# Analog_Mux.net
KiCad netlist of a schematic drawn in Altium Designer
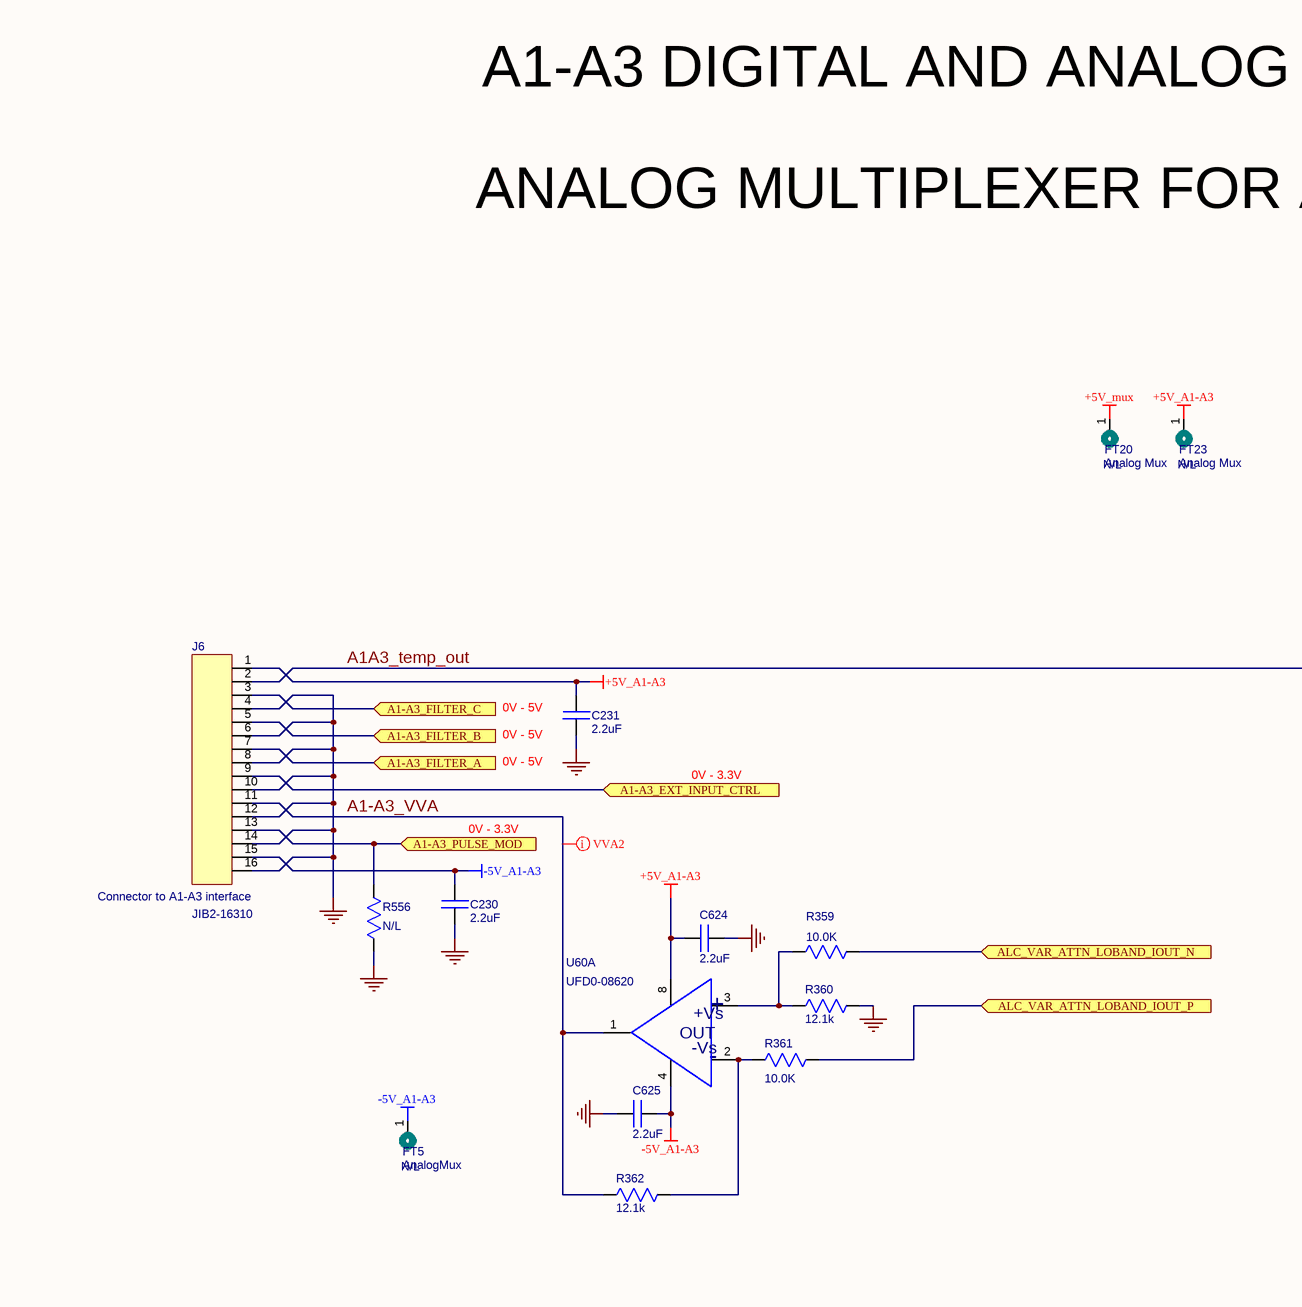
[diagram p0: Analog Mux.SchDoc, top left]
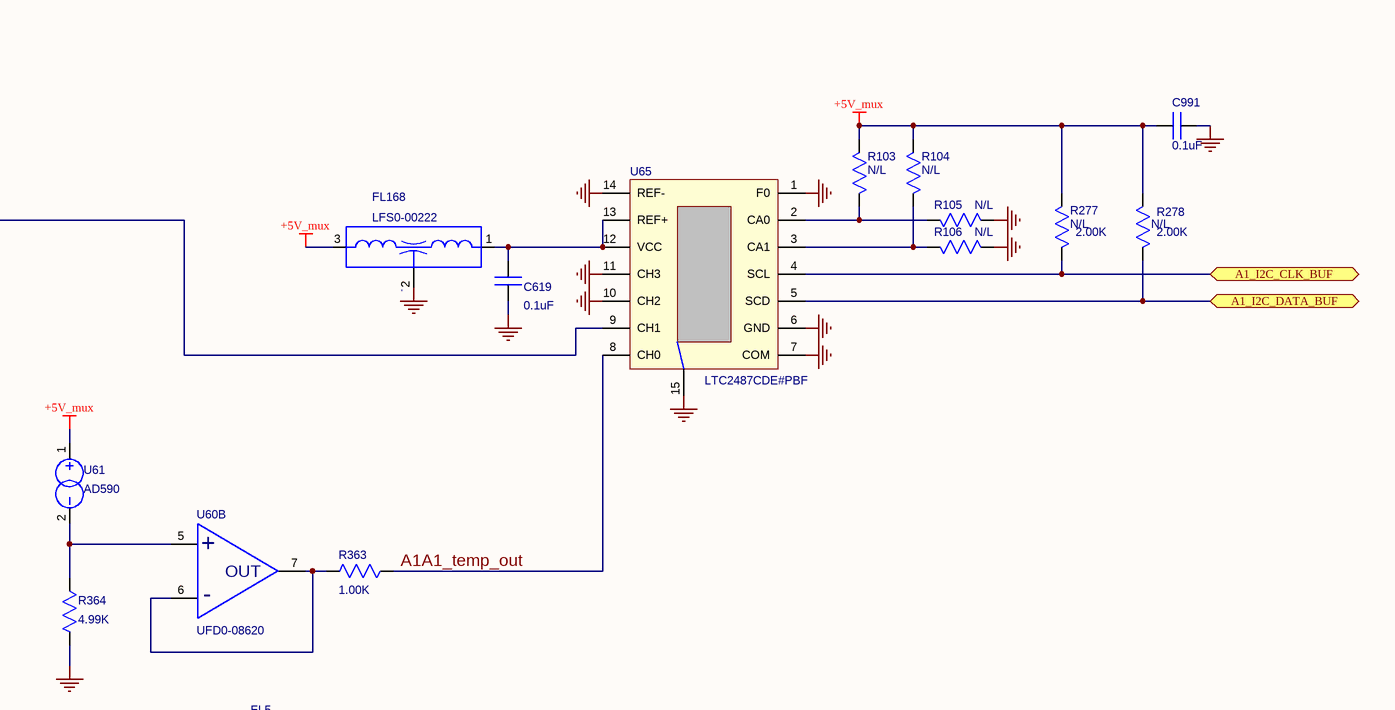
[diagram p1: Analog Mux.SchDoc, top right]
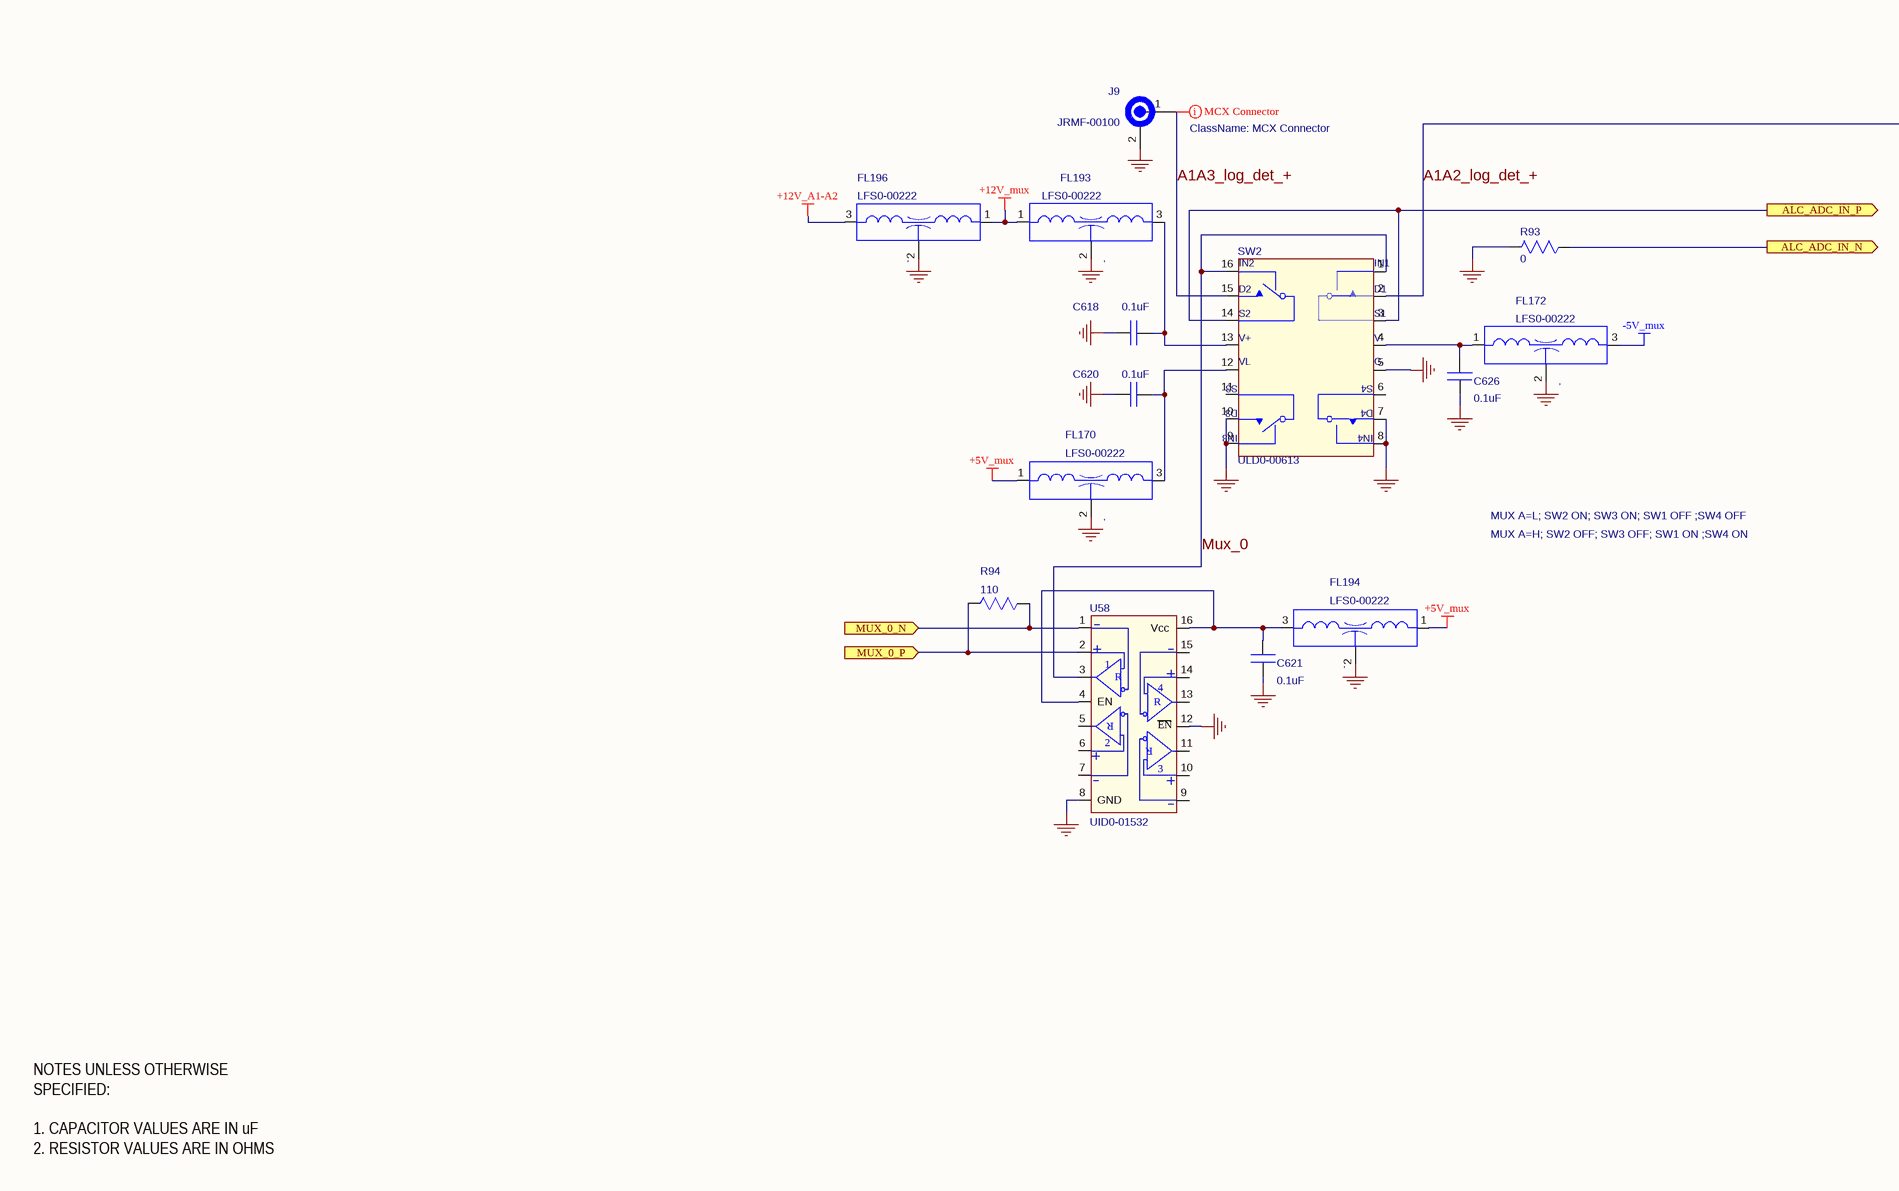
[diagram p2: Analog Mux.SchDoc, bottom left]
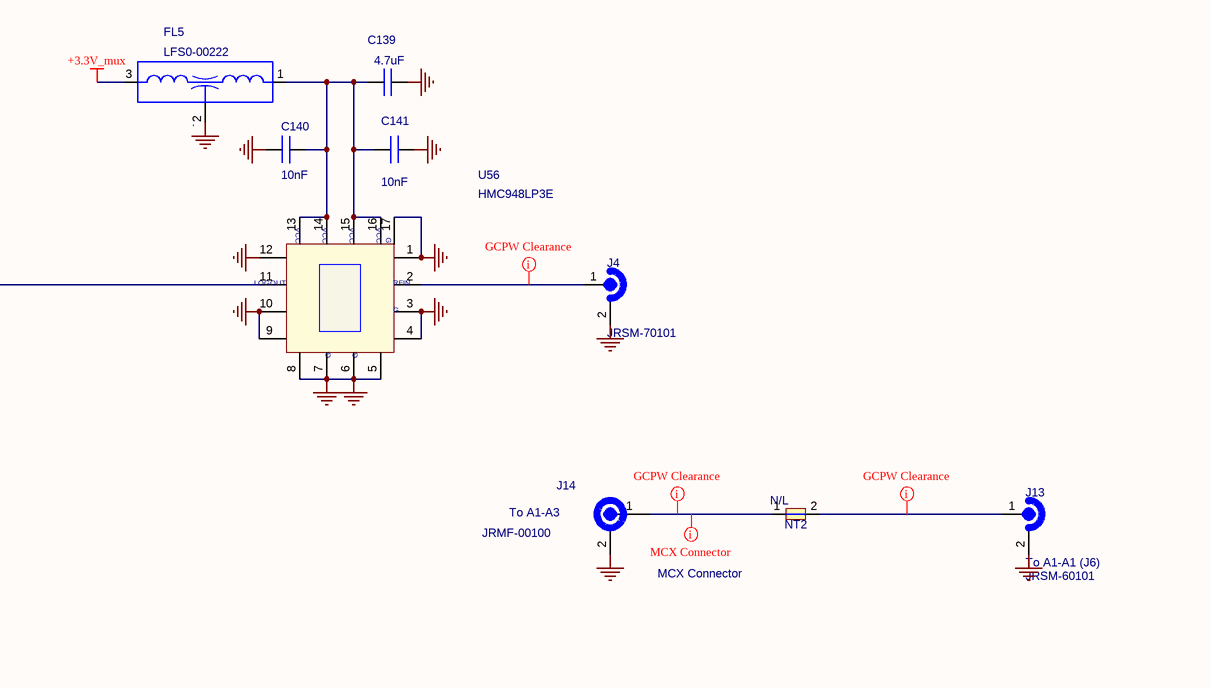
[diagram p3: Analog Mux.SchDoc, bottom right]

(export (version "E")
  (design (tool "Eeschema 10.0.6"))
  (components
    (comp (ref "C139")
      (value "4.7uF")
      (footprint "CAP-0805-N")
      (description "4.7uF 25V X5R CHIP CERAMIC")
      (fields (field (name "APPROVED") "CL"))
      (libsource (lib "Giga-tronics") (part "CK50-15470"))
    )
    (comp (ref "C140")
      (value "10nF")
      (footprint "CAP-0402-N")
      (description "10nF;10%;X7R;16 WVDC;CHIP;0402")
      (fields (field (name "APPROVED") "CL"))
      (libsource (lib "Giga-tronics") (part "TCC3-03100"))
    )
    (comp (ref "C141")
      (value "10nF")
      (footprint "CAP-0402-N")
      (description "10nF;10%;X7R;16 WVDC;CHIP;0402")
      (fields (field (name "APPROVED") "CL"))
      (libsource (lib "Giga-tronics") (part "TCC3-03100"))
    )
    (comp (ref "C230")
      (value "2.2uF")
      (footprint "CAP-0603-H035-N")
      (description "CAP,CHP,2.2UF,10%,X5R;16V")
      (fields (field (name "APPROVED") "CL"))
      (libsource (lib "Giga-tronics") (part "CK45-05220"))
    )
    (comp (ref "C231")
      (value "2.2uF")
      (footprint "CAP-0603-H035-N")
      (description "CAP,CHP,2.2UF,10%,X5R;16V")
      (fields (field (name "APPROVED") "CL"))
      (libsource (lib "Giga-tronics") (part "CK45-05220"))
    )
    (comp (ref "C618")
      (value "0.1uF")
      (footprint "CAP-0805-N")
      (description ".1UF;10%;X7R;>25V;CHIP;0805")
      (fields (field (name "APPROVED") "CL"))
      (libsource (lib "Giga-tronics") (part "CK50-04100"))
    )
    (comp (ref "C619")
      (value "0.1uF")
      (footprint "CAP-0805-N")
      (description ".1UF;10%;X7R;>25V;CHIP;0805")
      (fields (field (name "APPROVED") "CL"))
      (libsource (lib "Giga-tronics") (part "CK50-04100"))
    )
    (comp (ref "C620")
      (value "0.1uF")
      (footprint "CAP-0805-N")
      (description ".1UF;10%;X7R;>25V;CHIP;0805")
      (fields (field (name "APPROVED") "CL"))
      (libsource (lib "Giga-tronics") (part "CK50-04100"))
    )
    (comp (ref "C621")
      (value "0.1uF")
      (footprint "CAP-0603-H035-N")
      (description ".1UF;10%;X7R;16V;CHIP;0603")
      (fields (field (name "APPROVED") "CL"))
      (libsource (lib "Giga-tronics") (part "CK45-04100"))
    )
    (comp (ref "C624")
      (value "2.2uF")
      (footprint "CAP-0603-H035-N")
      (description "CAP,CHP,2.2UF,10%,X5R;16V")
      (fields (field (name "APPROVED") "CL"))
      (libsource (lib "Giga-tronics") (part "CK45-05220"))
    )
    (comp (ref "C625")
      (value "2.2uF")
      (footprint "CAP-0603-H035-N")
      (description "CAP,CHP,2.2UF,10%,X5R;16V")
      (fields (field (name "APPROVED") "CL"))
      (libsource (lib "Giga-tronics") (part "CK45-05220"))
    )
    (comp (ref "C626")
      (value "0.1uF")
      (footprint "CAP-0805-N")
      (description ".1UF;10%;X7R;>25V;CHIP;0805")
      (fields (field (name "APPROVED") "CL"))
      (libsource (lib "Giga-tronics") (part "CK50-04100"))
    )
    (comp (ref "C991")
      (value "0.1uF")
      (footprint "CAP-0402-N")
      (description ".1 UF,10%;X7R;16V,CHIP;0402")
      (fields (field (name "APPROVED") "CL"))
      (libsource (lib "Giga-tronics") (part "CK40-04100"))
    )
    (comp (ref "FL5")
      (value "Filter EMI 2200PF,1206")
      (footprint "FIL-NFE31P-1206-4P")
      (fields (field (name "G_PN") "LFS0-00222") (field (name "APPROVED") "CL"))
      (libsource (lib "Giga-tronics") (part "LFS0-00222"))
    )
    (comp (ref "FL168")
      (value "Filter EMI 2200PF,1206")
      (footprint "FIL-NFE31P-1206-4P")
      (fields (field (name "G_PN") "LFS0-00222") (field (name "APPROVED") "CL"))
      (libsource (lib "Giga-tronics") (part "LFS0-00222"))
    )
    (comp (ref "FL170")
      (value "Filter EMI 2200PF,1206")
      (footprint "FIL-NFE31P-1206-4P")
      (fields (field (name "G_PN") "LFS0-00222") (field (name "APPROVED") "CL"))
      (libsource (lib "") (part "LFS0-00222_1"))
    )
    (comp (ref "FL172")
      (value "Filter EMI 2200PF,1206")
      (footprint "FIL-NFE31P-1206-4P")
      (fields (field (name "G_PN") "LFS0-00222") (field (name "APPROVED") "CL"))
      (libsource (lib "") (part "LFS0-00222_1"))
    )
    (comp (ref "FL193")
      (value "Filter EMI 2200PF,1206")
      (footprint "FIL-NFE31P-1206-4P")
      (fields (field (name "G_PN") "LFS0-00222") (field (name "APPROVED") "CL"))
      (libsource (lib "") (part "LFS0-00222_1"))
    )
    (comp (ref "FL194")
      (value "Filter EMI 2200PF,1206")
      (footprint "FIL-NFE31P-1206-4P")
      (fields (field (name "G_PN") "LFS0-00222") (field (name "APPROVED") "CL"))
      (libsource (lib "Giga-tronics") (part "LFS0-00222"))
    )
    (comp (ref "FL196")
      (value "Filter EMI 2200PF,1206")
      (footprint "FIL-NFE31P-1206-4P")
      (fields (field (name "G_PN") "LFS0-00222") (field (name "APPROVED") "CL"))
      (libsource (lib "Giga-tronics") (part "LFS0-00222"))
    )
    (comp (ref "FT5")
      (value "AnalogMux")
      (footprint "FromToNode_ML2")
      (fields (field (name "NOLOAD") "N/L") (field (name "APPROVED") "*"))
      (libsource (lib "Giga-tronics") (part "FromToNode"))
    )
    (comp (ref "FT20")
      (value "Analog Mux")
      (footprint "FromToNode_ML2")
      (fields (field (name "NOLOAD") "N/L") (field (name "APPROVED") "*"))
      (libsource (lib "Giga-tronics") (part "FromToNode"))
    )
    (comp (ref "FT23")
      (value "Analog Mux")
      (footprint "FromToNode_ML2")
      (fields (field (name "NOLOAD") "N/L") (field (name "APPROVED") "*"))
      (libsource (lib "Giga-tronics") (part "FromToNode"))
    )
    (comp (ref "J4")
      (value ".")
      (footprint "JRSM-70101")
      (description "SMPM FD MALE,STRAIGHT SMT, R/A COPLANAR, 4 PIN THRU-HOLE")
      (fields (field (name "G_PN") "JRSM-70101") (field (name "APPROVED") "CL"))
      (libsource (lib "Giga-tronics") (part "JRSM-70101"))
    )
    (comp (ref "J6")
      (value "Connector to A1-A3 interface")
      (footprint "JIB2-16310")
      (description "STRIPLINE SOCKET;2MM CTR;2X8 PIN;.31\" HT")
      (fields (field (name "G_PN") "JIB2-16310") (field (name "APPROVED") "NM"))
      (libsource (lib "Giga-tronics") (part "JIB2-16310"))
    )
    (comp (ref "J9")
      (value "A1A3 log det +")
      (footprint "JRMF-00100")
      (description "MCX F;PC MOUNT;STRAIGHT;.1 LEADSP")
      (fields (field (name "G_PN") "JRMF-00100") (field (name "APPROVED") "NM"))
      (libsource (lib "Giga-tronics") (part "JRMF-00100"))
    )
    (comp (ref "J13")
      (value "To A1-A1 (J6)")
      (footprint "JRSM-60101")
      (description "SMPM SM MALE,STRAIGHT SMT, R/A COPLANAR, 4 PIN THRU-HOLE")
      (fields (field (name "G_PN") "JRSM-60101") (field (name "APPROVED") "CL"))
      (libsource (lib "Giga-tronics") (part "JRSM-60101"))
    )
    (comp (ref "J14")
      (value "To A1-A3")
      (footprint "JRMF-00100")
      (description "MCX F;PC MOUNT;STRAIGHT;.1 LEADSP")
      (fields (field (name "G_PN") "JRMF-00100") (field (name "APPROVED") "NM"))
      (libsource (lib "Giga-tronics") (part "JRMF-00100"))
    )
    (comp (ref "NT2")
      (value "NET TIE, 10 mil line")
      (footprint "NET_TIE_10mil")
      (fields (field (name "NOLOAD") "N/L") (field (name "APPROVED") "CL"))
      (libsource (lib "Giga-tronics") (part "NET_TIE_10mil"))
    )
    (comp (ref "R93")
      (value "0")
      (footprint "RES-0402-N")
      (description "JUMPER;0 OHMS;SMT;0402")
      (fields (field (name "APPROVED") "CL"))
      (libsource (lib "Giga-tronics") (part "RK35-00000"))
    )
    (comp (ref "R94")
      (value "110")
      (footprint "RES-0402-N")
      (description "110 OHMS; 1%; .1W; 100PPM; FILM; CHIP; 0402")
      (fields (field (name "APPROVED") "CL"))
      (libsource (lib "Giga-tronics") (part "RK35-01100"))
    )
    (comp (ref "R103")
      (value "2.00K OHMS;.06W;1%;200PPM;FILM;CHIP;0402")
      (footprint "RES-0402-N")
      (fields (field (name "NOLOAD") "N/L") (field (name "APPROVED") "CL"))
      (libsource (lib "Giga-tronics") (part "RK35-12000"))
    )
    (comp (ref "R104")
      (value "2.00K OHMS;.06W;1%;200PPM;FILM;CHIP;0402")
      (footprint "RES-0402-N")
      (fields (field (name "NOLOAD") "N/L") (field (name "APPROVED") "CL"))
      (libsource (lib "Giga-tronics") (part "RK35-12000"))
    )
    (comp (ref "R105")
      (value "JUMPER;0 OHMS;SMT;0402")
      (footprint "RES-0402-N")
      (fields (field (name "NOLOAD") "N/L") (field (name "APPROVED") "CL"))
      (libsource (lib "Giga-tronics") (part "RK35-00000"))
    )
    (comp (ref "R106")
      (value "JUMPER;0 OHMS;SMT;0402")
      (footprint "RES-0402-N")
      (fields (field (name "NOLOAD") "N/L") (field (name "APPROVED") "CL"))
      (libsource (lib "Giga-tronics") (part "RK35-00000"))
    )
    (comp (ref "R277")
      (value "2.00K")
      (footprint "RES-0402-N")
      (description "2.00K OHMS;.06W;1%;200PPM;FILM;CHIP;0402")
      (fields (field (name "NOLOAD") "N/L") (field (name "APPROVED") "CL"))
      (libsource (lib "Giga-tronics") (part "RK35-12000"))
    )
    (comp (ref "R278")
      (value "2.00K")
      (footprint "RES-0402-N")
      (description "2.00K OHMS;.06W;1%;200PPM;FILM;CHIP;0402")
      (fields (field (name "NOLOAD") "N/L") (field (name "APPROVED") "CL"))
      (libsource (lib "Giga-tronics") (part "RK35-12000"))
    )
    (comp (ref "R359")
      (value "10.0K")
      (footprint "RES-0402-N")
      (description "10.0K OHMS;.06W;1%;200PPM;FILM;CHIP;0402")
      (fields (field (name "APPROVED") "CL"))
      (libsource (lib "Giga-tronics") (part "RK35-21000"))
    )
    (comp (ref "R360")
      (value "12.1k")
      (footprint "RES-0402-N")
      (description "12.1K OHMS;.06W;1%;200PPM;FILM;CHIP;0402")
      (fields (field (name "APPROVED") "CL"))
      (libsource (lib "Giga-tronics") (part "RK35-21210"))
    )
    (comp (ref "R361")
      (value "10.0K")
      (footprint "RES-0402-N")
      (description "10.0K OHMS;.06W;1%;200PPM;FILM;CHIP;0402")
      (fields (field (name "APPROVED") "CL"))
      (libsource (lib "Giga-tronics") (part "RK35-21000"))
    )
    (comp (ref "R362")
      (value "12.1k")
      (footprint "RES-0402-N")
      (description "12.1K OHMS;.06W;1%;200PPM;FILM;CHIP;0402")
      (fields (field (name "APPROVED") "CL"))
      (libsource (lib "Giga-tronics") (part "RK35-21210"))
    )
    (comp (ref "R363")
      (value "1.00K")
      (footprint "RES-0402-N")
      (description "1.0K OHMS;.06W;1%;200PPM;FILM;CHIP;0402")
      (fields (field (name "APPROVED") "CL"))
      (libsource (lib "Giga-tronics") (part "RK35-11000"))
    )
    (comp (ref "R364")
      (value "4.99K")
      (footprint "RES-0402-N")
      (description "4.99K OHMS;.06W;1%;200PPM;FILM;CHIP;0402")
      (fields (field (name "APPROVED") "CL"))
      (libsource (lib "Giga-tronics") (part "RK35-14990"))
    )
    (comp (ref "R556")
      (value "100 OHMS; 1%; .1W; 100PPM; FILM; CHIP; 0402")
      (footprint "RES-0402-N")
      (fields (field (name "NOLOAD") "N/L") (field (name "APPROVED") "CL"))
      (libsource (lib "Giga-tronics") (part "RK35-01000"))
    )
    (comp (ref "SW2")
      (value "QUAD SPST ANALOG SW;200NS;45 OHM;SO-16")
      (footprint "SOIC-16_Vishay")
      (fields (field (name "G_PN") "ULD0-00613") (field (name "APPROVED") "NM"))
      (libsource (lib "Giga-tronics") (part "ULD0-00613"))
    )
    (comp (ref "U56")
      (value "LOG DETECTOR;1-23 GHz;54dB DYNAMIC RANGE;3x3 mm SMT")
      (footprint "QFN-16_HITTITE_LP3")
      (fields (field (name "M_PN") "HMC948LP3E") (field (name "APPROVED") "CL"))
      (libsource (lib "Giga-tronics") (part "MD00-00123"))
    )
    (comp (ref "U58")
      (value "UID0-01532")
      (footprint "Hydra_Ref_A1-A3:MTC16")
      (description "FIN1532 5V LVDS 4-Bit High Speed Differential Receiver;16-Lead TSSOP Package")
      (fields (field (name "APPROVED") "XiaoXiao"))
      (libsource (lib "Giga-tronics") (part "UID0-01532"))
    )
    (comp (ref "U60")
      (value "OP-AMP;DUAL:PRECISION;LOW CURRENT;LOW NOISE;WIDE")
      (footprint "SO8_MS-012")
      (fields (field (name "G_PN") "UFD0-08620") (field (name "APPROVED") "CL"))
      (libsource (lib "Giga-tronics") (part "UFD0-08620"))
    )
    (comp (ref "U61")
      (value "IC; 2-Terminal; Temperature Transducer")
      (footprint "TO-52")
      (fields (field (name "M_PN") "AD590") (field (name "APPROVED") "NM"))
      (libsource (lib "Hydra_Ref_Charles_Computer_4_30_12") (part "18729"))
    )
    (comp (ref "U65")
      (value "ADC;16-BIT;2/4 CHANNEL;12SPS;INT REF;5V SUP;QFN14")
      (footprint "DFN14-LINEAR")
      (fields (field (name "M_PN") "LTC2487CDE#PBF") (field (name "APPROVED") "CL"))
      (libsource (lib "Giga-tronics") (part "UID0-02487"))
    )
  )
  (nets
    (net (code "1") (name "+3.3V_mux") (class "Default")
      (node (ref "FL5") (pin "3") (pinfunction "OUT_3") (pintype "passive"))
    )
    (net (code "2") (name "+5V_A1-A3") (class "Default")
      (node (ref "C231") (pin "1") (pintype "passive"))
      (node (ref "C624") (pin "1") (pintype "passive"))
      (node (ref "FT23") (pin "1") (pinfunction "1_1") (pintype "passive"))
      (node (ref "J6") (pin "1") (pintype "passive"))
      (node (ref "U60") (pin "8") (pinfunction "V+_8") (pintype "passive"))
    )
    (net (code "3") (name "+5V_mux") (class "Default")
      (node (ref "C991") (pin "2") (pintype "passive"))
      (node (ref "FL168") (pin "3") (pinfunction "OUT_3") (pintype "passive"))
      (node (ref "FL170") (pin "1") (pinfunction "IN_1") (pintype "passive"))
      (node (ref "FL194") (pin "1") (pinfunction "IN_1") (pintype "passive"))
      (node (ref "FT20") (pin "1") (pinfunction "1_1") (pintype "passive"))
      (node (ref "R103") (pin "2") (pintype "passive"))
      (node (ref "R104") (pin "2") (pintype "passive"))
      (node (ref "R277") (pin "2") (pintype "passive"))
      (node (ref "R278") (pin "2") (pintype "passive"))
      (node (ref "U61") (pin "1") (pinfunction "+_1") (pintype "passive"))
    )
    (net (code "4") (name "+12V_A1-A2") (class "Default")
      (node (ref "FL196") (pin "3") (pinfunction "OUT_3") (pintype "passive"))
    )
    (net (code "5") (name "+12V_mux") (class "Default")
      (node (ref "FL193") (pin "1") (pinfunction "IN_1") (pintype "passive"))
      (node (ref "FL196") (pin "1") (pinfunction "IN_1") (pintype "passive"))
    )
    (net (code "6") (name "-5V_A1-A3") (class "Default")
      (node (ref "C230") (pin "1") (pintype "passive"))
      (node (ref "C625") (pin "1") (pintype "passive"))
      (node (ref "FT5") (pin "1") (pinfunction "1_1") (pintype "passive"))
      (node (ref "J6") (pin "15") (pintype "passive"))
      (node (ref "U60") (pin "4") (pinfunction "V-_4") (pintype "passive"))
    )
    (net (code "7") (name "-5V_mux") (class "Default")
      (node (ref "FL172") (pin "3") (pinfunction "OUT_3") (pintype "passive"))
    )
    (net (code "8") (name "/A1-A3_EXT_INPUT_CTRL") (class "Default")
      (node (ref "J6") (pin "9") (pintype "passive"))
    )
    (net (code "9") (name "/A1-A3_FILTER_A") (class "Default")
      (node (ref "J6") (pin "7") (pintype "passive"))
    )
    (net (code "10") (name "/A1-A3_FILTER_B") (class "Default")
      (node (ref "J6") (pin "5") (pintype "passive"))
    )
    (net (code "11") (name "/A1-A3_FILTER_C") (class "Default")
      (node (ref "J6") (pin "3") (pintype "passive"))
    )
    (net (code "12") (name "/A1-A3_PULSE_MOD") (class "Default")
      (node (ref "J6") (pin "13") (pintype "passive"))
      (node (ref "R556") (pin "1") (pintype "passive"))
    )
    (net (code "13") (name "/A1-A3_VVA") (class "Default")
      (node (ref "J6") (pin "11") (pintype "passive"))
      (node (ref "R362") (pin "1") (pintype "passive"))
      (node (ref "U60") (pin "1") (pinfunction "OUT_1") (pintype "passive"))
    )
    (net (code "14") (name "/A1A1_temp_out") (class "Default")
      (node (ref "R363") (pin "2") (pintype "passive"))
      (node (ref "U65") (pin "8") (pinfunction "CH0_8") (pintype "passive"))
    )
    (net (code "15") (name "/A1A2_log_det_+") (class "Default")
      (node (ref "SW2") (pin "2") (pinfunction "D1_2") (pintype "passive"))
      (node (ref "U56") (pin "11") (pinfunction "LOGOUT_11") (pintype "passive"))
    )
    (net (code "16") (name "/A1A3_log_det_+") (class "Default")
      (node (ref "J9") (pin "1") (pinfunction "1_1") (pintype "passive"))
      (node (ref "SW2") (pin "15") (pinfunction "D2_15") (pintype "passive"))
    )
    (net (code "17") (name "/A1A3_temp_out") (class "Default")
      (node (ref "J6") (pin "2") (pintype "passive"))
      (node (ref "U65") (pin "9") (pinfunction "CH1_9") (pintype "passive"))
    )
    (net (code "18") (name "/A1_I2C_CLK_BUF") (class "Default")
      (node (ref "R277") (pin "1") (pintype "passive"))
      (node (ref "U65") (pin "4") (pinfunction "SCL_4") (pintype "passive"))
    )
    (net (code "19") (name "/A1_I2C_DATA_BUF") (class "Default")
      (node (ref "R278") (pin "1") (pintype "passive"))
      (node (ref "U65") (pin "5") (pinfunction "SCD_5") (pintype "passive"))
    )
    (net (code "20") (name "/ALC_ADC_IN_N") (class "Default")
      (node (ref "R93") (pin "2") (pintype "passive"))
    )
    (net (code "21") (name "/ALC_ADC_IN_P") (class "Default")
      (node (ref "SW2") (pin "14") (pinfunction "S2_14") (pintype "passive"))
      (node (ref "SW2") (pin "3") (pinfunction "S1_3") (pintype "passive"))
    )
    (net (code "22") (name "/ALC_VAR_ATTN_LOBAND_IOUT_N") (class "Default")
      (node (ref "R359") (pin "2") (pintype "passive"))
    )
    (net (code "23") (name "/ALC_VAR_ATTN_LOBAND_IOUT_P") (class "Default")
      (node (ref "R361") (pin "2") (pintype "passive"))
    )
    (net (code "24") (name "/MUX_0_N") (class "Default")
      (node (ref "R94") (pin "2") (pintype "passive"))
      (node (ref "U58") (pin "1") (pinfunction "Rin1-_1") (pintype "passive"))
    )
    (net (code "25") (name "/MUX_0_P") (class "Default")
      (node (ref "R94") (pin "1") (pintype "passive"))
      (node (ref "U58") (pin "2") (pinfunction "Rin1+_2") (pintype "passive"))
    )
    (net (code "26") (name "/Mux_0") (class "Default")
      (node (ref "SW2") (pin "1") (pinfunction "IN1_1") (pintype "passive"))
      (node (ref "SW2") (pin "16") (pinfunction "IN2_16") (pintype "passive"))
      (node (ref "U58") (pin "3") (pinfunction "Rout1_3") (pintype "passive"))
    )
    (net (code "27") (name "GND") (class "Default")
      (node (ref "C139") (pin "1") (pintype "passive"))
      (node (ref "C140") (pin "1") (pintype "passive"))
      (node (ref "C141") (pin "1") (pintype "passive"))
      (node (ref "C230") (pin "2") (pintype "passive"))
      (node (ref "C231") (pin "2") (pintype "passive"))
      (node (ref "C618") (pin "1") (pintype "passive"))
      (node (ref "C619") (pin "1") (pintype "passive"))
      (node (ref "C620") (pin "1") (pintype "passive"))
      (node (ref "C621") (pin "2") (pintype "passive"))
      (node (ref "C624") (pin "2") (pintype "passive"))
      (node (ref "C625") (pin "2") (pintype "passive"))
      (node (ref "C626") (pin "1") (pintype "passive"))
      (node (ref "C991") (pin "1") (pintype "passive"))
      (node (ref "FL168") (pin "2") (pinfunction "GND_2") (pintype "passive"))
      (node (ref "FL170") (pin "2") (pinfunction "GND_2") (pintype "passive"))
      (node (ref "FL172") (pin "2") (pinfunction "GND_2") (pintype "passive"))
      (node (ref "FL193") (pin "2") (pinfunction "GND_2") (pintype "passive"))
      (node (ref "FL194") (pin "2") (pinfunction "GND_2") (pintype "passive"))
      (node (ref "FL196") (pin "2") (pinfunction "GND_2") (pintype "passive"))
      (node (ref "FL5") (pin "2") (pinfunction "GND_2") (pintype "passive"))
      (node (ref "J13") (pin "2") (pinfunction "GND_2") (pintype "passive"))
      (node (ref "J14") (pin "2") (pinfunction "GND_2") (pintype "passive"))
      (node (ref "J4") (pin "2") (pinfunction "GND_2") (pintype "passive"))
      (node (ref "J6") (pin "10") (pintype "passive"))
      (node (ref "J6") (pin "12") (pintype "passive"))
      (node (ref "J6") (pin "14") (pintype "passive"))
      (node (ref "J6") (pin "16") (pintype "passive"))
      (node (ref "J6") (pin "4") (pintype "passive"))
      (node (ref "J6") (pin "6") (pintype "passive"))
      (node (ref "J6") (pin "8") (pintype "passive"))
      (node (ref "J9") (pin "2") (pinfunction "GND_2") (pintype "passive"))
      (node (ref "R105") (pin "2") (pintype "passive"))
      (node (ref "R106") (pin "2") (pintype "passive"))
      (node (ref "R360") (pin "2") (pintype "passive"))
      (node (ref "R364") (pin "1") (pintype "passive"))
      (node (ref "R556") (pin "2") (pintype "passive"))
      (node (ref "R93") (pin "1") (pintype "passive"))
      (node (ref "SW2") (pin "10") (pinfunction "D3_10") (pintype "passive"))
      (node (ref "SW2") (pin "5") (pinfunction "G_5") (pintype "passive"))
      (node (ref "SW2") (pin "7") (pinfunction "D4_7") (pintype "passive"))
      (node (ref "SW2") (pin "8") (pinfunction "IN4_8") (pintype "passive"))
      (node (ref "SW2") (pin "9") (pinfunction "IN3_9") (pintype "passive"))
      (node (ref "U56") (pin "1") (pinfunction "NC_1") (pintype "passive"))
      (node (ref "U56") (pin "10") (pinfunction "NC_10") (pintype "passive"))
      (node (ref "U56") (pin "12") (pinfunction "NC_12") (pintype "passive"))
      (node (ref "U56") (pin "17") (pinfunction "GND_17") (pintype "passive"))
      (node (ref "U56") (pin "3") (pinfunction "G_3") (pintype "passive"))
      (node (ref "U56") (pin "4") (pinfunction "NC_4") (pintype "passive"))
      (node (ref "U56") (pin "5") (pinfunction "NC_5") (pintype "passive"))
      (node (ref "U56") (pin "6") (pinfunction "G_6") (pintype "passive"))
      (node (ref "U56") (pin "7") (pinfunction "G_7") (pintype "passive"))
      (node (ref "U56") (pin "8") (pinfunction "NC_8") (pintype "passive"))
      (node (ref "U56") (pin "9") (pinfunction "NC_9") (pintype "passive"))
      (node (ref "U58") (pin "12") (pinfunction "EN_Rev_12") (pintype "passive"))
      (node (ref "U58") (pin "8") (pinfunction "GND_8") (pintype "power_in"))
      (node (ref "U65") (pin "1") (pinfunction "F0_1") (pintype "passive"))
      (node (ref "U65") (pin "10") (pinfunction "CH2_10") (pintype "passive"))
      (node (ref "U65") (pin "11") (pinfunction "CH3_11") (pintype "passive"))
      (node (ref "U65") (pin "14") (pinfunction "REF-_14") (pintype "passive"))
      (node (ref "U65") (pin "15") (pinfunction "PADDLE_15") (pintype "passive"))
      (node (ref "U65") (pin "6") (pinfunction "GND_6") (pintype "passive"))
      (node (ref "U65") (pin "7") (pinfunction "COM_7") (pintype "passive"))
    )
    (net (code "28") (name "Net-(FL5-IN)") (class "Default")
      (node (ref "C139") (pin "2") (pintype "passive"))
      (node (ref "C140") (pin "2") (pintype "passive"))
      (node (ref "C141") (pin "2") (pintype "passive"))
      (node (ref "FL5") (pin "1") (pinfunction "IN_1") (pintype "passive"))
      (node (ref "U56") (pin "13") (pinfunction "VCC_13") (pintype "passive"))
      (node (ref "U56") (pin "14") (pinfunction "VCC_14") (pintype "passive"))
      (node (ref "U56") (pin "15") (pinfunction "NC_15") (pintype "passive"))
      (node (ref "U56") (pin "16") (pinfunction "VCC_16") (pintype "passive"))
    )
    (net (code "29") (name "Net-(FL168-IN)") (class "Default")
      (node (ref "C619") (pin "2") (pintype "passive"))
      (node (ref "FL168") (pin "1") (pinfunction "IN_1") (pintype "passive"))
      (node (ref "U65") (pin "12") (pinfunction "VCC_12") (pintype "passive"))
      (node (ref "U65") (pin "13") (pinfunction "REF+_13") (pintype "passive"))
    )
    (net (code "30") (name "Net-(FL170-OUT)") (class "Default")
      (node (ref "C620") (pin "2") (pintype "passive"))
      (node (ref "FL170") (pin "3") (pinfunction "OUT_3") (pintype "passive"))
      (node (ref "SW2") (pin "12") (pinfunction "VL_12") (pintype "passive"))
    )
    (net (code "31") (name "Net-(FL172-IN)") (class "Default")
      (node (ref "C626") (pin "2") (pintype "passive"))
      (node (ref "FL172") (pin "1") (pinfunction "IN_1") (pintype "passive"))
      (node (ref "SW2") (pin "4") (pinfunction "V-_4") (pintype "passive"))
    )
    (net (code "32") (name "Net-(FL193-OUT)") (class "Default")
      (node (ref "C618") (pin "2") (pintype "passive"))
      (node (ref "FL193") (pin "3") (pinfunction "OUT_3") (pintype "passive"))
      (node (ref "SW2") (pin "13") (pinfunction "V+_13") (pintype "passive"))
    )
    (net (code "33") (name "Net-(FL194-OUT)") (class "Default")
      (node (ref "C621") (pin "1") (pintype "passive"))
      (node (ref "FL194") (pin "3") (pinfunction "OUT_3") (pintype "passive"))
      (node (ref "U58") (pin "16") (pinfunction "Vcc_16") (pintype "power_in"))
      (node (ref "U58") (pin "4") (pinfunction "EN_4") (pintype "passive"))
    )
    (net (code "34") (name "Net-(J4-CNTR)") (class "Default")
      (node (ref "J4") (pin "1") (pinfunction "CNTR_1") (pintype "passive"))
      (node (ref "U56") (pin "2") (pinfunction "RFIN_2") (pintype "passive"))
    )
    (net (code "35") (name "Net-(J13-CNTR)") (class "Default")
      (node (ref "J13") (pin "1") (pinfunction "CNTR_1") (pintype "passive"))
      (node (ref "NT2") (pin "2") (pintype "passive"))
    )
    (net (code "36") (name "Net-(J14-Pad1)") (class "Default")
      (node (ref "J14") (pin "1") (pinfunction "1_1") (pintype "passive"))
      (node (ref "NT2") (pin "1") (pintype "passive"))
    )
    (net (code "37") (name "Net-(U60A-+IN)") (class "Default")
      (node (ref "R359") (pin "1") (pintype "passive"))
      (node (ref "R360") (pin "1") (pintype "passive"))
      (node (ref "U60") (pin "3") (pinfunction "+IN_3") (pintype "passive"))
    )
    (net (code "38") (name "Net-(U60A--IN)") (class "Default")
      (node (ref "R361") (pin "1") (pintype "passive"))
      (node (ref "R362") (pin "2") (pintype "passive"))
      (node (ref "U60") (pin "2") (pinfunction "-IN_2") (pintype "passive"))
    )
    (net (code "39") (name "Net-(U60B-+IN)") (class "Default")
      (node (ref "R364") (pin "2") (pintype "passive"))
      (node (ref "U60") (pin "5") (pinfunction "+IN_5") (pintype "passive"))
      (node (ref "U61") (pin "2") (pinfunction "-_2") (pintype "passive"))
    )
    (net (code "40") (name "Net-(U60B--IN)") (class "Default")
      (node (ref "R363") (pin "1") (pintype "passive"))
      (node (ref "U60") (pin "6") (pinfunction "-IN_6") (pintype "passive"))
      (node (ref "U60") (pin "7") (pinfunction "OUT_7") (pintype "passive"))
    )
    (net (code "41") (name "Net-(U65-CA0)") (class "Default")
      (node (ref "R103") (pin "1") (pintype "passive"))
      (node (ref "R105") (pin "1") (pintype "passive"))
      (node (ref "U65") (pin "2") (pinfunction "CA0_2") (pintype "passive"))
    )
    (net (code "42") (name "Net-(U65-CA1)") (class "Default")
      (node (ref "R104") (pin "1") (pintype "passive"))
      (node (ref "R106") (pin "1") (pintype "passive"))
      (node (ref "U65") (pin "3") (pinfunction "CA1_3") (pintype "passive"))
    )
    (net (code "43") (name "unconnected-(SW2-S3-Pad11)") (class "Default")
      (node (ref "SW2") (pin "11") (pinfunction "S3_11") (pintype "passive"))
    )
    (net (code "44") (name "unconnected-(SW2-S4-Pad6)") (class "Default")
      (node (ref "SW2") (pin "6") (pinfunction "S4_6") (pintype "passive"))
    )
    (net (code "45") (name "unconnected-(U58-Rin2+-Pad6)") (class "Default")
      (node (ref "U58") (pin "6") (pinfunction "Rin2+_6") (pintype "passive"))
    )
    (net (code "46") (name "unconnected-(U58-Rin2--Pad7)") (class "Default")
      (node (ref "U58") (pin "7") (pinfunction "Rin2-_7") (pintype "passive"))
    )
    (net (code "47") (name "unconnected-(U58-Rin3+-Pad10)") (class "Default")
      (node (ref "U58") (pin "10") (pinfunction "Rin3+_10") (pintype "passive"))
    )
    (net (code "48") (name "unconnected-(U58-Rin3--Pad9)") (class "Default")
      (node (ref "U58") (pin "9") (pinfunction "Rin3-_9") (pintype "passive"))
    )
    (net (code "49") (name "unconnected-(U58-Rin4+-Pad14)") (class "Default")
      (node (ref "U58") (pin "14") (pinfunction "Rin4+_14") (pintype "passive"))
    )
    (net (code "50") (name "unconnected-(U58-Rin4--Pad15)") (class "Default")
      (node (ref "U58") (pin "15") (pinfunction "Rin4-_15") (pintype "passive"))
    )
    (net (code "51") (name "unconnected-(U58-Rout2-Pad5)") (class "Default")
      (node (ref "U58") (pin "5") (pinfunction "Rout2_5") (pintype "passive"))
    )
    (net (code "52") (name "unconnected-(U58-Rout3-Pad11)") (class "Default")
      (node (ref "U58") (pin "11") (pinfunction "Rout3_11") (pintype "passive"))
    )
    (net (code "53") (name "unconnected-(U58-Rout4-Pad13)") (class "Default")
      (node (ref "U58") (pin "13") (pinfunction "Rout4_13") (pintype "passive"))
    )
  )
)
